# UnidadDeControl-STM.net
KiCad netlist of a schematic drawn in Altium Designer
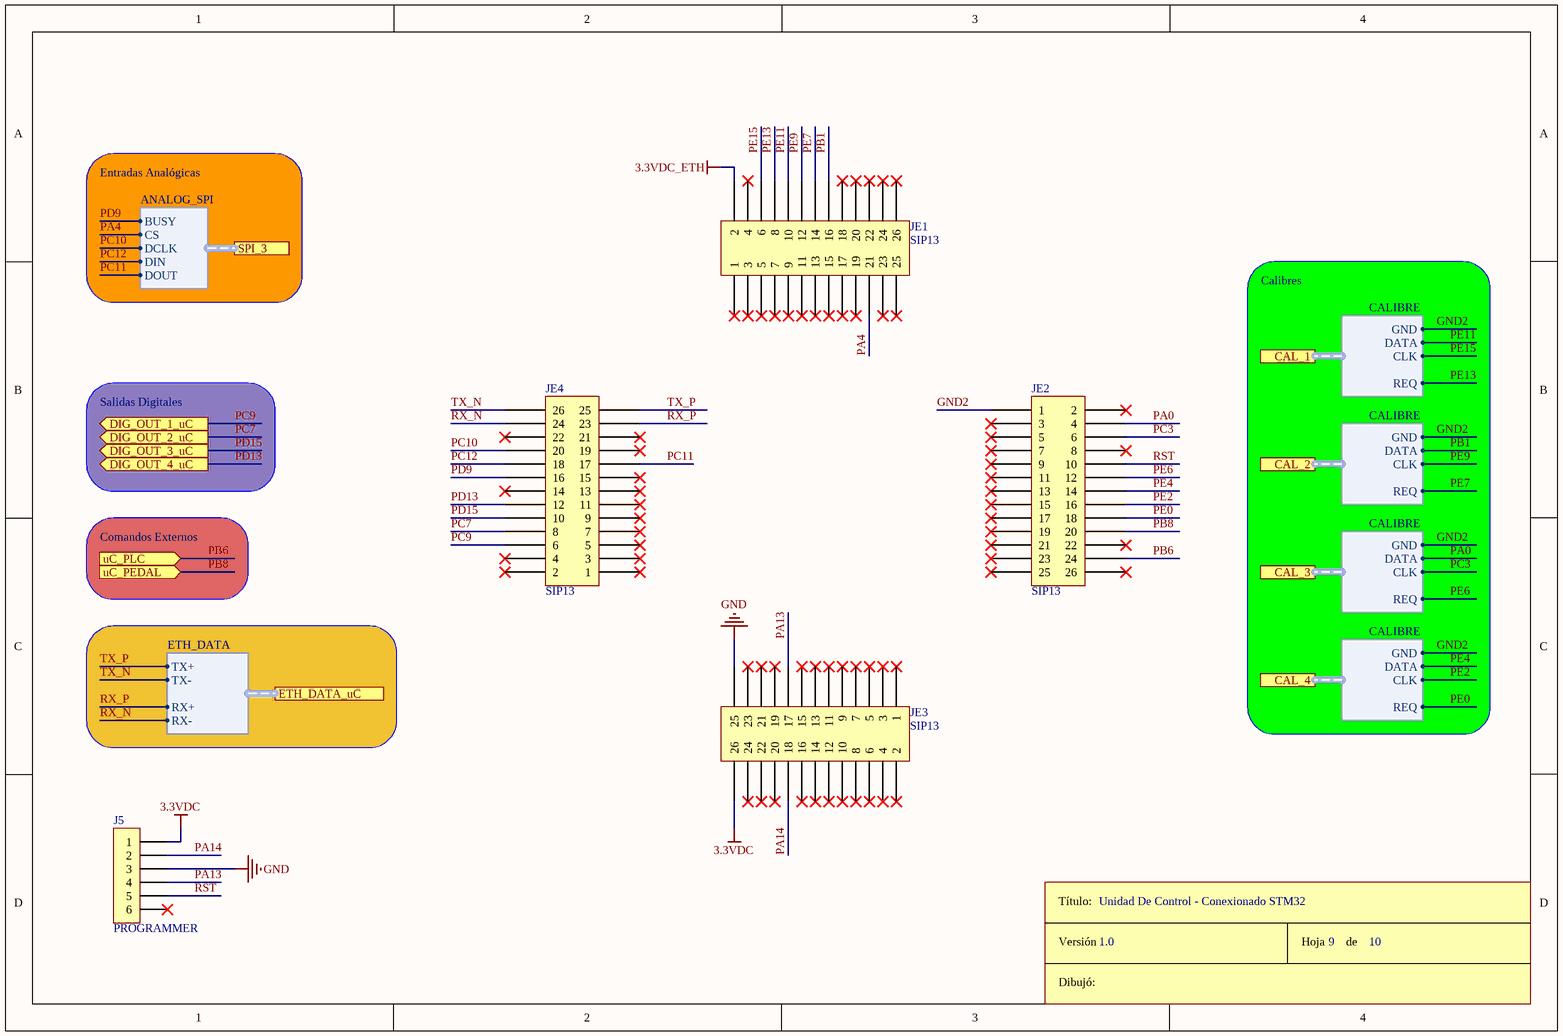
[diagram p0: UnidadDeControl-STM.SchDoc]

(export (version "E")
  (design (tool "Eeschema 10.0.6"))
  (components
    (comp (ref "J5") (value "PROGRAMMER") (footprint "SIP6") (libsource (lib "LIBEBAL") (part "CON6")))
    (comp (ref "JE1") (value "SIP13") (footprint "SIP13*2 - HDR") (libsource (lib "") (part "CON13*2_1")))
    (comp (ref "JE2") (value "SIP13") (footprint "SIP13*2 - HDR") (libsource (lib "") (part "CON13*2_3")))
    (comp (ref "JE3")
      (value "SIP13")
      (footprint "SIP13*2 - HDR")
      (libsource (lib "AditionalComponents") (part "CON13*2"))
    )
    (comp (ref "JE4") (value "SIP13") (footprint "SIP13*2 - HDR") (libsource (lib "") (part "CON13*2_2")))
    (comp (ref "ROT8") (value "Rótulo") (libsource (lib "LIB PIO IX") (part "Rótulo")))
  )
  (nets
    (net (code "4") (name "/GND2") (class "Default")
      (node (ref "JE2") (pin "1") (pinfunction "1_1") (pintype "passive"))
    )
    (net (code "5") (name "/PA0") (class "Default")
      (node (ref "JE2") (pin "4") (pinfunction "4_4") (pintype "passive"))
    )
    (net (code "6") (name "/PA4") (class "Default")
      (node (ref "JE1") (pin "21") (pinfunction "21_21") (pintype "passive"))
    )
    (net (code "7") (name "/PA13") (class "Default")
      (node (ref "J5") (pin "4") (pinfunction "4_4") (pintype "passive"))
      (node (ref "JE3") (pin "17") (pinfunction "17_17") (pintype "passive"))
    )
    (net (code "8") (name "/PA14") (class "Default")
      (node (ref "J5") (pin "2") (pinfunction "2_2") (pintype "passive"))
      (node (ref "JE3") (pin "18") (pinfunction "18_18") (pintype "passive"))
    )
    (net (code "9") (name "/PB1") (class "Default")
      (node (ref "JE1") (pin "16") (pinfunction "16_16") (pintype "passive"))
    )
    (net (code "10") (name "/PB6") (class "Default")
      (node (ref "JE2") (pin "24") (pinfunction "24_24") (pintype "passive"))
    )
    (net (code "11") (name "/PB8") (class "Default")
      (node (ref "JE2") (pin "20") (pinfunction "20_20") (pintype "passive"))
    )
    (net (code "12") (name "/PC3") (class "Default")
      (node (ref "JE2") (pin "6") (pinfunction "6_6") (pintype "passive"))
    )
    (net (code "13") (name "/PC7") (class "Default")
      (node (ref "JE4") (pin "8") (pinfunction "8_8") (pintype "passive"))
    )
    (net (code "14") (name "/PC9") (class "Default")
      (node (ref "JE4") (pin "6") (pinfunction "6_6") (pintype "passive"))
    )
    (net (code "15") (name "/PC10") (class "Default")
      (node (ref "JE4") (pin "20") (pinfunction "20_20") (pintype "passive"))
    )
    (net (code "16") (name "/PC11") (class "Default")
      (node (ref "JE4") (pin "17") (pinfunction "17_17") (pintype "passive"))
    )
    (net (code "17") (name "/PC12") (class "Default")
      (node (ref "JE4") (pin "18") (pinfunction "18_18") (pintype "passive"))
    )
    (net (code "18") (name "/PD9") (class "Default")
      (node (ref "JE4") (pin "16") (pinfunction "16_16") (pintype "passive"))
    )
    (net (code "19") (name "/PD13") (class "Default")
      (node (ref "JE4") (pin "12") (pinfunction "12_12") (pintype "passive"))
    )
    (net (code "20") (name "/PD15") (class "Default")
      (node (ref "JE4") (pin "10") (pinfunction "10_10") (pintype "passive"))
    )
    (net (code "21") (name "/PE0") (class "Default")
      (node (ref "JE2") (pin "18") (pinfunction "18_18") (pintype "passive"))
    )
    (net (code "22") (name "/PE2") (class "Default")
      (node (ref "JE2") (pin "16") (pinfunction "16_16") (pintype "passive"))
    )
    (net (code "23") (name "/PE4") (class "Default")
      (node (ref "JE2") (pin "14") (pinfunction "14_14") (pintype "passive"))
    )
    (net (code "24") (name "/PE6") (class "Default")
      (node (ref "JE2") (pin "12") (pinfunction "12_12") (pintype "passive"))
    )
    (net (code "25") (name "/PE7") (class "Default")
      (node (ref "JE1") (pin "14") (pinfunction "14_14") (pintype "passive"))
    )
    (net (code "26") (name "/PE9") (class "Default")
      (node (ref "JE1") (pin "12") (pinfunction "12_12") (pintype "passive"))
    )
    (net (code "27") (name "/PE11") (class "Default")
      (node (ref "JE1") (pin "10") (pinfunction "10_10") (pintype "passive"))
    )
    (net (code "28") (name "/PE13") (class "Default")
      (node (ref "JE1") (pin "8") (pinfunction "8_8") (pintype "passive"))
    )
    (net (code "29") (name "/PE15") (class "Default")
      (node (ref "JE1") (pin "6") (pinfunction "6_6") (pintype "passive"))
    )
    (net (code "30") (name "/RST") (class "Default")
      (node (ref "J5") (pin "5") (pinfunction "5_5") (pintype "passive"))
      (node (ref "JE2") (pin "10") (pinfunction "10_10") (pintype "passive"))
    )
    (net (code "31") (name "/RX_N") (class "Default")
      (node (ref "JE4") (pin "24") (pinfunction "24_24") (pintype "passive"))
    )
    (net (code "32") (name "/RX_P") (class "Default")
      (node (ref "JE4") (pin "23") (pinfunction "23_23") (pintype "passive"))
    )
    (net (code "33") (name "/TX_N") (class "Default")
      (node (ref "JE4") (pin "26") (pinfunction "26_26") (pintype "passive"))
    )
    (net (code "34") (name "/TX_P") (class "Default")
      (node (ref "JE4") (pin "25") (pinfunction "25_25") (pintype "passive"))
    )
    (net (code "38") (name "3.3VDC") (class "Default")
      (node (ref "J5") (pin "1") (pinfunction "1_1") (pintype "passive"))
      (node (ref "JE3") (pin "26") (pinfunction "26_26") (pintype "passive"))
    )
    (net (code "39") (name "3.3VDC_ETH") (class "Default")
      (node (ref "JE1") (pin "2") (pinfunction "2_2") (pintype "passive"))
    )
    (net (code "40") (name "GND") (class "Default")
      (node (ref "J5") (pin "3") (pinfunction "3_3") (pintype "passive"))
      (node (ref "JE3") (pin "25") (pinfunction "25_25") (pintype "passive"))
    )
    (net (code "41") (name "unconnected-(J5-Pad6)") (class "Default")
      (node (ref "J5") (pin "6") (pinfunction "6_6") (pintype "passive+no_connect"))
    )
    (net (code "42") (name "unconnected-(JE1-Pad1)") (class "Default")
      (node (ref "JE1") (pin "1") (pinfunction "1_1") (pintype "passive+no_connect"))
    )
    (net (code "43") (name "unconnected-(JE1-Pad3)") (class "Default")
      (node (ref "JE1") (pin "3") (pinfunction "3_3") (pintype "passive+no_connect"))
    )
    (net (code "44") (name "unconnected-(JE1-Pad4)") (class "Default")
      (node (ref "JE1") (pin "4") (pinfunction "4_4") (pintype "passive+no_connect"))
    )
    (net (code "45") (name "unconnected-(JE1-Pad5)") (class "Default")
      (node (ref "JE1") (pin "5") (pinfunction "5_5") (pintype "passive+no_connect"))
    )
    (net (code "46") (name "unconnected-(JE1-Pad7)") (class "Default")
      (node (ref "JE1") (pin "7") (pinfunction "7_7") (pintype "passive+no_connect"))
    )
    (net (code "47") (name "unconnected-(JE1-Pad9)") (class "Default")
      (node (ref "JE1") (pin "9") (pinfunction "9_9") (pintype "passive+no_connect"))
    )
    (net (code "48") (name "unconnected-(JE1-Pad11)") (class "Default")
      (node (ref "JE1") (pin "11") (pinfunction "11_11") (pintype "passive+no_connect"))
    )
    (net (code "49") (name "unconnected-(JE1-Pad13)") (class "Default")
      (node (ref "JE1") (pin "13") (pinfunction "13_13") (pintype "passive+no_connect"))
    )
    (net (code "50") (name "unconnected-(JE1-Pad15)") (class "Default")
      (node (ref "JE1") (pin "15") (pinfunction "15_15") (pintype "passive+no_connect"))
    )
    (net (code "51") (name "unconnected-(JE1-Pad17)") (class "Default")
      (node (ref "JE1") (pin "17") (pinfunction "17_17") (pintype "passive+no_connect"))
    )
    (net (code "52") (name "unconnected-(JE1-Pad18)") (class "Default")
      (node (ref "JE1") (pin "18") (pinfunction "18_18") (pintype "passive+no_connect"))
    )
    (net (code "53") (name "unconnected-(JE1-Pad19)") (class "Default")
      (node (ref "JE1") (pin "19") (pinfunction "19_19") (pintype "passive+no_connect"))
    )
    (net (code "54") (name "unconnected-(JE1-Pad20)") (class "Default")
      (node (ref "JE1") (pin "20") (pinfunction "20_20") (pintype "passive+no_connect"))
    )
    (net (code "55") (name "unconnected-(JE1-Pad22)") (class "Default")
      (node (ref "JE1") (pin "22") (pinfunction "22_22") (pintype "passive+no_connect"))
    )
    (net (code "56") (name "unconnected-(JE1-Pad23)") (class "Default")
      (node (ref "JE1") (pin "23") (pinfunction "23_23") (pintype "passive+no_connect"))
    )
    (net (code "57") (name "unconnected-(JE1-Pad24)") (class "Default")
      (node (ref "JE1") (pin "24") (pinfunction "24_24") (pintype "passive+no_connect"))
    )
    (net (code "58") (name "unconnected-(JE1-Pad25)") (class "Default")
      (node (ref "JE1") (pin "25") (pinfunction "25_25") (pintype "passive+no_connect"))
    )
    (net (code "59") (name "unconnected-(JE1-Pad26)") (class "Default")
      (node (ref "JE1") (pin "26") (pinfunction "26_26") (pintype "passive+no_connect"))
    )
    (net (code "60") (name "unconnected-(JE2-Pad2)") (class "Default")
      (node (ref "JE2") (pin "2") (pinfunction "2_2") (pintype "passive+no_connect"))
    )
    (net (code "61") (name "unconnected-(JE2-Pad3)") (class "Default")
      (node (ref "JE2") (pin "3") (pinfunction "3_3") (pintype "passive+no_connect"))
    )
    (net (code "62") (name "unconnected-(JE2-Pad5)") (class "Default")
      (node (ref "JE2") (pin "5") (pinfunction "5_5") (pintype "passive+no_connect"))
    )
    (net (code "63") (name "unconnected-(JE2-Pad7)") (class "Default")
      (node (ref "JE2") (pin "7") (pinfunction "7_7") (pintype "passive+no_connect"))
    )
    (net (code "64") (name "unconnected-(JE2-Pad8)") (class "Default")
      (node (ref "JE2") (pin "8") (pinfunction "8_8") (pintype "passive+no_connect"))
    )
    (net (code "65") (name "unconnected-(JE2-Pad9)") (class "Default")
      (node (ref "JE2") (pin "9") (pinfunction "9_9") (pintype "passive+no_connect"))
    )
    (net (code "66") (name "unconnected-(JE2-Pad11)") (class "Default")
      (node (ref "JE2") (pin "11") (pinfunction "11_11") (pintype "passive+no_connect"))
    )
    (net (code "67") (name "unconnected-(JE2-Pad13)") (class "Default")
      (node (ref "JE2") (pin "13") (pinfunction "13_13") (pintype "passive+no_connect"))
    )
    (net (code "68") (name "unconnected-(JE2-Pad15)") (class "Default")
      (node (ref "JE2") (pin "15") (pinfunction "15_15") (pintype "passive+no_connect"))
    )
    (net (code "69") (name "unconnected-(JE2-Pad17)") (class "Default")
      (node (ref "JE2") (pin "17") (pinfunction "17_17") (pintype "passive+no_connect"))
    )
    (net (code "70") (name "unconnected-(JE2-Pad19)") (class "Default")
      (node (ref "JE2") (pin "19") (pinfunction "19_19") (pintype "passive+no_connect"))
    )
    (net (code "71") (name "unconnected-(JE2-Pad21)") (class "Default")
      (node (ref "JE2") (pin "21") (pinfunction "21_21") (pintype "passive+no_connect"))
    )
    (net (code "72") (name "unconnected-(JE2-Pad22)") (class "Default")
      (node (ref "JE2") (pin "22") (pinfunction "22_22") (pintype "passive+no_connect"))
    )
    (net (code "73") (name "unconnected-(JE2-Pad23)") (class "Default")
      (node (ref "JE2") (pin "23") (pinfunction "23_23") (pintype "passive+no_connect"))
    )
    (net (code "74") (name "unconnected-(JE2-Pad25)") (class "Default")
      (node (ref "JE2") (pin "25") (pinfunction "25_25") (pintype "passive+no_connect"))
    )
    (net (code "75") (name "unconnected-(JE2-Pad26)") (class "Default")
      (node (ref "JE2") (pin "26") (pinfunction "26_26") (pintype "passive+no_connect"))
    )
    (net (code "76") (name "unconnected-(JE3-Pad1)") (class "Default")
      (node (ref "JE3") (pin "1") (pinfunction "1_1") (pintype "passive+no_connect"))
    )
    (net (code "77") (name "unconnected-(JE3-Pad2)") (class "Default")
      (node (ref "JE3") (pin "2") (pinfunction "2_2") (pintype "passive+no_connect"))
    )
    (net (code "78") (name "unconnected-(JE3-Pad3)") (class "Default")
      (node (ref "JE3") (pin "3") (pinfunction "3_3") (pintype "passive+no_connect"))
    )
    (net (code "79") (name "unconnected-(JE3-Pad4)") (class "Default")
      (node (ref "JE3") (pin "4") (pinfunction "4_4") (pintype "passive+no_connect"))
    )
    (net (code "80") (name "unconnected-(JE3-Pad5)") (class "Default")
      (node (ref "JE3") (pin "5") (pinfunction "5_5") (pintype "passive+no_connect"))
    )
    (net (code "81") (name "unconnected-(JE3-Pad6)") (class "Default")
      (node (ref "JE3") (pin "6") (pinfunction "6_6") (pintype "passive+no_connect"))
    )
    (net (code "82") (name "unconnected-(JE3-Pad7)") (class "Default")
      (node (ref "JE3") (pin "7") (pinfunction "7_7") (pintype "passive+no_connect"))
    )
    (net (code "83") (name "unconnected-(JE3-Pad8)") (class "Default")
      (node (ref "JE3") (pin "8") (pinfunction "8_8") (pintype "passive+no_connect"))
    )
    (net (code "84") (name "unconnected-(JE3-Pad9)") (class "Default")
      (node (ref "JE3") (pin "9") (pinfunction "9_9") (pintype "passive+no_connect"))
    )
    (net (code "85") (name "unconnected-(JE3-Pad10)") (class "Default")
      (node (ref "JE3") (pin "10") (pinfunction "10_10") (pintype "passive+no_connect"))
    )
    (net (code "86") (name "unconnected-(JE3-Pad11)") (class "Default")
      (node (ref "JE3") (pin "11") (pinfunction "11_11") (pintype "passive+no_connect"))
    )
    (net (code "87") (name "unconnected-(JE3-Pad12)") (class "Default")
      (node (ref "JE3") (pin "12") (pinfunction "12_12") (pintype "passive+no_connect"))
    )
    (net (code "88") (name "unconnected-(JE3-Pad13)") (class "Default")
      (node (ref "JE3") (pin "13") (pinfunction "13_13") (pintype "passive+no_connect"))
    )
    (net (code "89") (name "unconnected-(JE3-Pad14)") (class "Default")
      (node (ref "JE3") (pin "14") (pinfunction "14_14") (pintype "passive+no_connect"))
    )
    (net (code "90") (name "unconnected-(JE3-Pad15)") (class "Default")
      (node (ref "JE3") (pin "15") (pinfunction "15_15") (pintype "passive+no_connect"))
    )
    (net (code "91") (name "unconnected-(JE3-Pad16)") (class "Default")
      (node (ref "JE3") (pin "16") (pinfunction "16_16") (pintype "passive+no_connect"))
    )
    (net (code "92") (name "unconnected-(JE3-Pad19)") (class "Default")
      (node (ref "JE3") (pin "19") (pinfunction "19_19") (pintype "passive+no_connect"))
    )
    (net (code "93") (name "unconnected-(JE3-Pad20)") (class "Default")
      (node (ref "JE3") (pin "20") (pinfunction "20_20") (pintype "passive+no_connect"))
    )
    (net (code "94") (name "unconnected-(JE3-Pad21)") (class "Default")
      (node (ref "JE3") (pin "21") (pinfunction "21_21") (pintype "passive+no_connect"))
    )
    (net (code "95") (name "unconnected-(JE3-Pad22)") (class "Default")
      (node (ref "JE3") (pin "22") (pinfunction "22_22") (pintype "passive+no_connect"))
    )
    (net (code "96") (name "unconnected-(JE3-Pad23)") (class "Default")
      (node (ref "JE3") (pin "23") (pinfunction "23_23") (pintype "passive+no_connect"))
    )
    (net (code "97") (name "unconnected-(JE3-Pad24)") (class "Default")
      (node (ref "JE3") (pin "24") (pinfunction "24_24") (pintype "passive+no_connect"))
    )
    (net (code "98") (name "unconnected-(JE4-Pad1)") (class "Default")
      (node (ref "JE4") (pin "1") (pinfunction "1_1") (pintype "passive+no_connect"))
    )
    (net (code "99") (name "unconnected-(JE4-Pad2)") (class "Default")
      (node (ref "JE4") (pin "2") (pinfunction "2_2") (pintype "passive+no_connect"))
    )
    (net (code "100") (name "unconnected-(JE4-Pad3)") (class "Default")
      (node (ref "JE4") (pin "3") (pinfunction "3_3") (pintype "passive+no_connect"))
    )
    (net (code "101") (name "unconnected-(JE4-Pad4)") (class "Default")
      (node (ref "JE4") (pin "4") (pinfunction "4_4") (pintype "passive+no_connect"))
    )
    (net (code "102") (name "unconnected-(JE4-Pad5)") (class "Default")
      (node (ref "JE4") (pin "5") (pinfunction "5_5") (pintype "passive+no_connect"))
    )
    (net (code "103") (name "unconnected-(JE4-Pad7)") (class "Default")
      (node (ref "JE4") (pin "7") (pinfunction "7_7") (pintype "passive+no_connect"))
    )
    (net (code "104") (name "unconnected-(JE4-Pad9)") (class "Default")
      (node (ref "JE4") (pin "9") (pinfunction "9_9") (pintype "passive+no_connect"))
    )
    (net (code "105") (name "unconnected-(JE4-Pad11)") (class "Default")
      (node (ref "JE4") (pin "11") (pinfunction "11_11") (pintype "passive+no_connect"))
    )
    (net (code "106") (name "unconnected-(JE4-Pad13)") (class "Default")
      (node (ref "JE4") (pin "13") (pinfunction "13_13") (pintype "passive+no_connect"))
    )
    (net (code "107") (name "unconnected-(JE4-Pad14)") (class "Default")
      (node (ref "JE4") (pin "14") (pinfunction "14_14") (pintype "passive+no_connect"))
    )
    (net (code "108") (name "unconnected-(JE4-Pad15)") (class "Default")
      (node (ref "JE4") (pin "15") (pinfunction "15_15") (pintype "passive+no_connect"))
    )
    (net (code "109") (name "unconnected-(JE4-Pad19)") (class "Default")
      (node (ref "JE4") (pin "19") (pinfunction "19_19") (pintype "passive+no_connect"))
    )
    (net (code "110") (name "unconnected-(JE4-Pad21)") (class "Default")
      (node (ref "JE4") (pin "21") (pinfunction "21_21") (pintype "passive+no_connect"))
    )
    (net (code "111") (name "unconnected-(JE4-Pad22)") (class "Default")
      (node (ref "JE4") (pin "22") (pinfunction "22_22") (pintype "passive+no_connect"))
    )
  )
)
